# Octo.net
KiCad netlist of a schematic drawn in Altium Designer
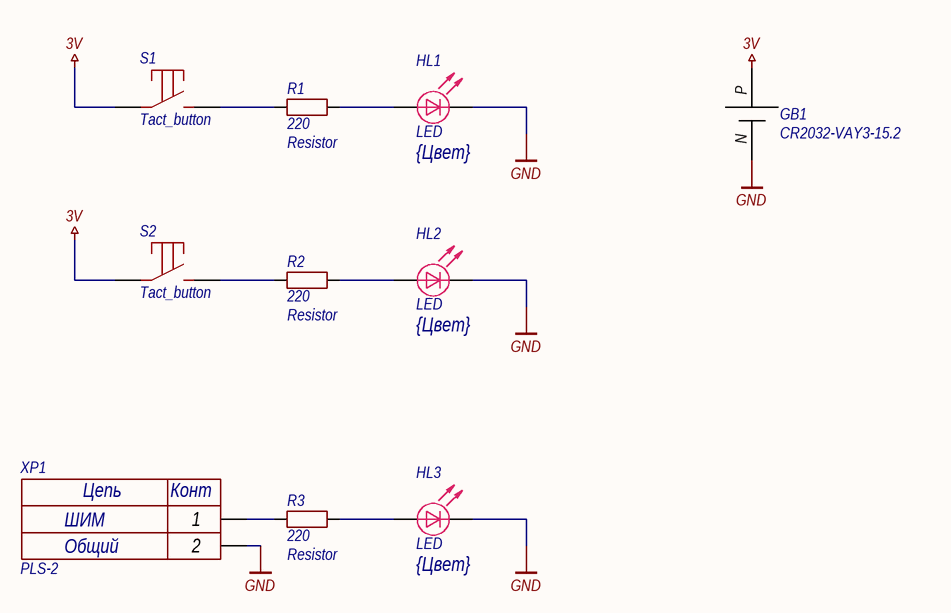
[diagram p0: Octo.SchDoc]

(export (version "E")
  (design (tool "Eeschema 10.0.6"))
  (components
    (comp (ref "GB1")
      (value "CR2032-VAY3-15.2")
      (footprint "CR2032-VAY3-15.2")
      (description "Li, MnO2 батарея типоразмера R20, 3В, 0.22Ач, приваренные выводы, -20...60 °C")
      (libsource (lib "Hydrolib") (part "Battery"))
    )
    (comp (ref "HL1")
      (value "LED")
      (footprint "3mm_led_red")
      (description "Светодиод")
      (fields (field (name "COLOR") "{Цвет}"))
      (libsource (lib "Hydrolib") (part "LED"))
    )
    (comp (ref "HL2")
      (value "LED")
      (footprint "3mm_led_red")
      (description "Светодиод")
      (fields (field (name "COLOR") "{Цвет}"))
      (libsource (lib "Hydrolib") (part "LED"))
    )
    (comp (ref "HL3")
      (value "LED")
      (footprint "3mm_led_red")
      (description "Светодиод")
      (fields (field (name "COLOR") "{Цвет}"))
      (libsource (lib "Hydrolib") (part "LED"))
    )
    (comp (ref "R1")
      (value "Resistor")
      (footprint "RES_THT_025W_220")
      (description "Резистор номиналом 220 Ом и точностью 1%")
      (fields
        (field (name "ALTIUM_VALUE") "220")
        (field (name "PART NUMBER") "Resistor_220_1_0603")
        (field (name "TOLERANCE") "1%")
      )
      (libsource (lib "Hydrolib") (part "Resistor"))
    )
    (comp (ref "R2")
      (value "Resistor")
      (footprint "RES_THT_025W_220")
      (description "Резистор номиналом 220 Ом и точностью 1%")
      (fields
        (field (name "ALTIUM_VALUE") "220")
        (field (name "PART NUMBER") "Resistor_220_1_0603")
        (field (name "TOLERANCE") "1%")
      )
      (libsource (lib "Hydrolib") (part "Resistor"))
    )
    (comp (ref "R3")
      (value "Resistor")
      (footprint "RES_THT_025W_220")
      (description "Резистор номиналом 220 Ом и точностью 1%")
      (fields
        (field (name "ALTIUM_VALUE") "220")
        (field (name "PART NUMBER") "Resistor_220_1_0603")
        (field (name "TOLERANCE") "1%")
      )
      (libsource (lib "Hydrolib") (part "Resistor"))
    )
    (comp (ref "S1")
      (value "Tact_button")
      (footprint "Button_tht_6X6")
      (description "Тактовая кнопка")
      (libsource (lib "Hydrolib") (part "Tact_button"))
    )
    (comp (ref "S2")
      (value "Tact_button")
      (footprint "Button_tht_6X6")
      (description "Тактовая кнопка")
      (libsource (lib "Hydrolib") (part "Tact_button"))
    )
    (comp (ref "XP1")
      (value "PLS-2")
      (footprint "PLS2")
      (description "Гребенка 2 пина")
      (fields (field (name "VALUE2") "Общий") (field (name "VALUE1") "ШИМ"))
      (libsource (lib "Hydrolib") (part "Conn_2pin"))
    )
  )
  (nets
    (net (code "1") (name "3V") (class "Default")
      (node (ref "GB1") (pin "P") (pinfunction "P_P") (pintype "passive"))
      (node (ref "S1") (pin "1") (pinfunction "1_1") (pintype "passive"))
      (node (ref "S2") (pin "1") (pinfunction "1_1") (pintype "passive"))
    )
    (net (code "2") (name "GND") (class "Default")
      (node (ref "GB1") (pin "N") (pinfunction "N_N") (pintype "passive"))
      (node (ref "HL1") (pin "2") (pinfunction "2_2") (pintype "passive"))
      (node (ref "HL2") (pin "2") (pinfunction "2_2") (pintype "passive"))
      (node (ref "HL3") (pin "2") (pinfunction "2_2") (pintype "passive"))
      (node (ref "XP1") (pin "2") (pinfunction "2_2") (pintype "passive"))
    )
    (net (code "3") (name "Net-(HL1-Pad1)") (class "Default")
      (node (ref "HL1") (pin "1") (pinfunction "1_1") (pintype "passive"))
      (node (ref "R1") (pin "2") (pinfunction "2_2") (pintype "passive"))
    )
    (net (code "4") (name "Net-(HL2-Pad1)") (class "Default")
      (node (ref "HL2") (pin "1") (pinfunction "1_1") (pintype "passive"))
      (node (ref "R2") (pin "2") (pinfunction "2_2") (pintype "passive"))
    )
    (net (code "5") (name "Net-(HL3-Pad1)") (class "Default")
      (node (ref "HL3") (pin "1") (pinfunction "1_1") (pintype "passive"))
      (node (ref "R3") (pin "2") (pinfunction "2_2") (pintype "passive"))
    )
    (net (code "6") (name "Net-(R1-Pad1)") (class "Default")
      (node (ref "R1") (pin "1") (pinfunction "1_1") (pintype "passive"))
      (node (ref "S1") (pin "2") (pinfunction "2_2") (pintype "passive"))
    )
    (net (code "7") (name "Net-(R2-Pad1)") (class "Default")
      (node (ref "R2") (pin "1") (pinfunction "1_1") (pintype "passive"))
      (node (ref "S2") (pin "2") (pinfunction "2_2") (pintype "passive"))
    )
    (net (code "8") (name "Net-(R3-Pad1)") (class "Default")
      (node (ref "R3") (pin "1") (pinfunction "1_1") (pintype "passive"))
      (node (ref "XP1") (pin "1") (pinfunction "1_1") (pintype "passive"))
    )
  )
)
